# Sensors.net
KiCad netlist of a schematic drawn in Altium Designer
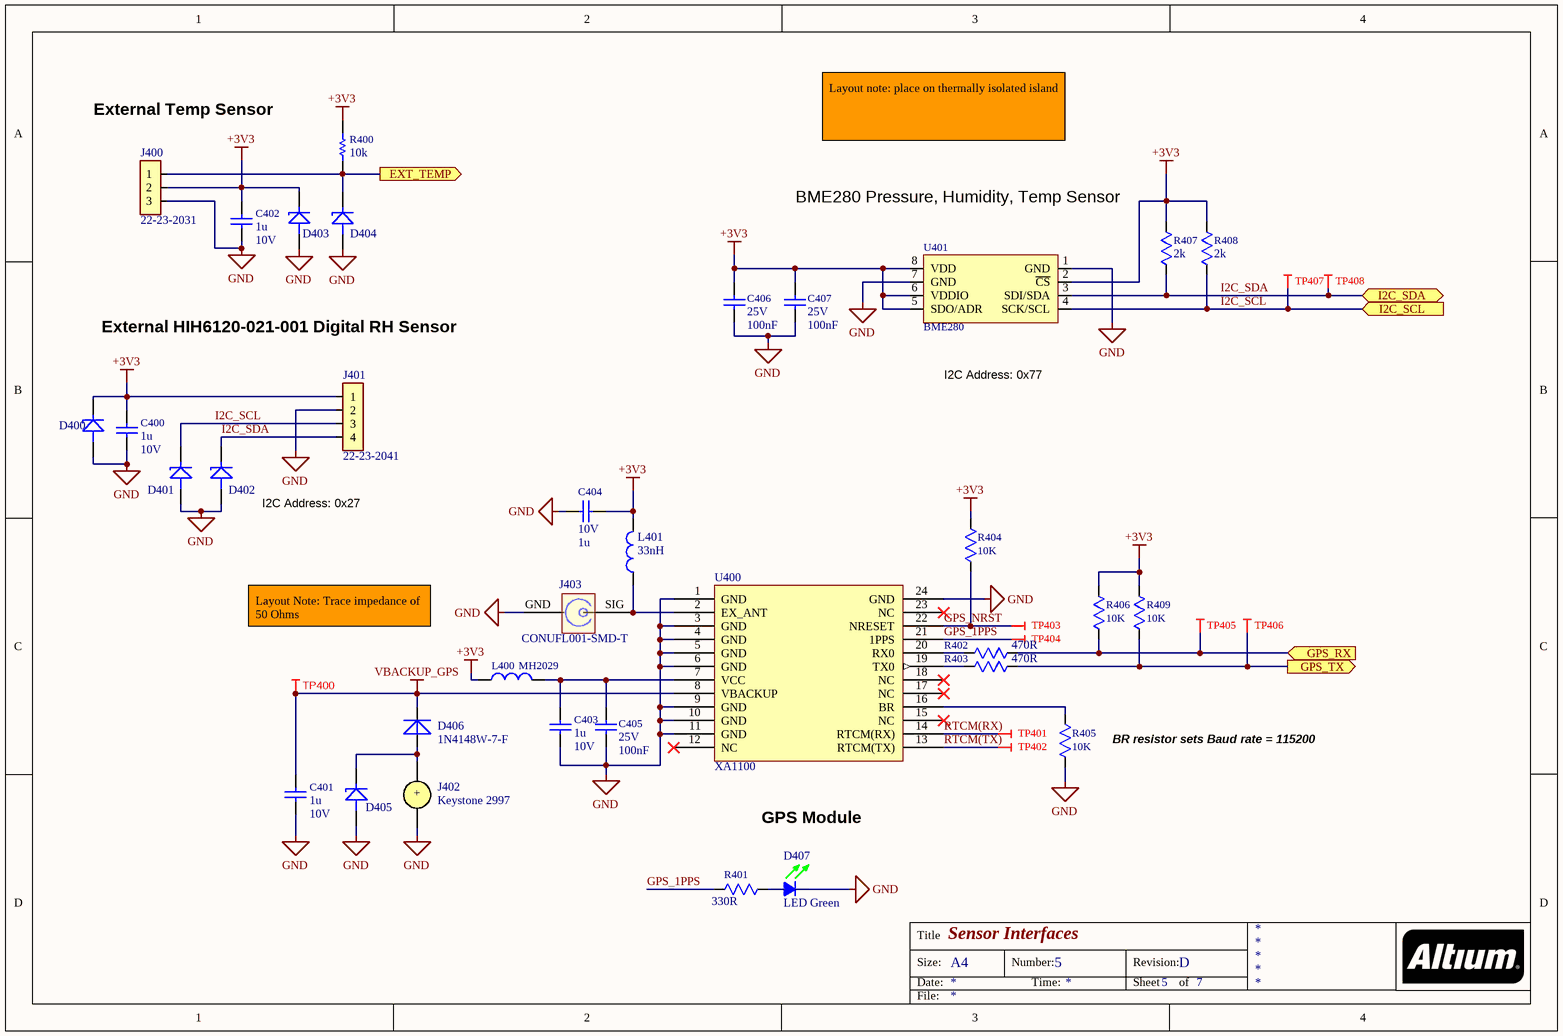
[diagram p0: Sensors.SchDoc]

(export (version "E")
  (design (tool "Eeschema 10.0.6"))
  (components
    (comp (ref "C400")
      (value "1u")
      (footprint "CAPC1005X06N")
      (description "CAP 4.7uF 10V ±10% X5R 0603")
      (fields
        (field (name "VOLTAGE") "10V")
        (field (name "MANUFACTURER PART NUMBER") "CL05A105MP5NNNC")
        (field (name "MANUFACTURER") "Samsung")
      )
      (libsource (lib "Capacitors") (part "4.7uF_0603_10V"))
    )
    (comp (ref "C401")
      (value "1u")
      (footprint "CAPC1005X06N")
      (description "CAP 4.7uF 10V ±10% X5R 0603")
      (fields
        (field (name "VOLTAGE") "10V")
        (field (name "MANUFACTURER PART NUMBER") "CL05A105MP5NNNC")
        (field (name "MANUFACTURER") "Samsung")
      )
      (libsource (lib "Capacitors") (part "4.7uF_0603_10V"))
    )
    (comp (ref "C402")
      (value "1u")
      (footprint "CAPC1005X06N")
      (description "CAP 4.7uF 10V ±10% X5R 0603")
      (fields
        (field (name "VOLTAGE") "10V")
        (field (name "MANUFACTURER PART NUMBER") "CL05A105MP5NNNC")
        (field (name "MANUFACTURER") "Samsung")
      )
      (libsource (lib "Capacitors") (part "4.7uF_0603_10V"))
    )
    (comp (ref "C403")
      (value "1u")
      (footprint "CAPC1005X06N")
      (description "CAP 4.7uF 10V ±10% X5R 0603")
      (fields
        (field (name "VOLTAGE") "10V")
        (field (name "MANUFACTURER PART NUMBER") "CL05A105MP5NNNC")
        (field (name "MANUFACTURER") "Samsung")
      )
      (libsource (lib "Capacitors") (part "4.7uF_0603_10V"))
    )
    (comp (ref "C404")
      (value "1u")
      (footprint "CAPC1005X06N")
      (description "CAP 4.7uF 10V ±10% X5R 0603")
      (fields
        (field (name "VOLTAGE") "10V")
        (field (name "MANUFACTURER PART NUMBER") "CL05A105MP5NNNC")
        (field (name "MANUFACTURER") "Samsung")
      )
      (libsource (lib "Capacitors") (part "4.7uF_0603_10V"))
    )
    (comp (ref "C405")
      (value "100nF")
      (footprint "CAPC1005X06N")
      (fields
        (field (name "VOLTAGE") "25V")
        (field (name "MANUFACTURER PART NUMBER") "CL05A104KA5NNNC")
        (field (name "MANUFACTURER") "Samsung")
        (field (name "Comment") "4.7uF")
      )
      (libsource (lib "Capacitors") (part "4.7uF_0603_10V"))
    )
    (comp (ref "C406")
      (value "100nF")
      (footprint "CAPC1005X06N")
      (fields
        (field (name "VOLTAGE") "25V")
        (field (name "MANUFACTURER PART NUMBER") "CL05A104KA5NNNC")
        (field (name "MANUFACTURER") "Samsung")
        (field (name "Comment") "4.7uF")
      )
      (libsource (lib "Capacitors") (part "4.7uF_0603_10V"))
    )
    (comp (ref "C407")
      (value "100nF")
      (footprint "CAPC1005X06N")
      (fields
        (field (name "VOLTAGE") "25V")
        (field (name "MANUFACTURER PART NUMBER") "CL05A104KA5NNNC")
        (field (name "MANUFACTURER") "Samsung")
        (field (name "Comment") "4.7uF")
      )
      (libsource (lib "Capacitors") (part "4.7uF_0603_10V"))
    )
    (comp (ref "D400")
      (value "3.3V TVS")
      (footprint "NXP PTVSxS1UR-Series (SOD123W)")
      (fields
        (field (name "MANUFACTURER") "Nexperia")
        (field (name "MANUFACTURER PART NUMBER") "PTVS3V3S1UTR,115")
      )
      (libsource (lib "FSM_2018") (part "NXP PTVSxS1UR-Series"))
    )
    (comp (ref "D401")
      (value "3.3V TVS")
      (footprint "NXP PTVSxS1UR-Series (SOD123W)")
      (fields
        (field (name "MANUFACTURER") "Nexperia")
        (field (name "MANUFACTURER PART NUMBER") "PTVS3V3S1UTR,115")
      )
      (libsource (lib "FSM_2018") (part "NXP PTVSxS1UR-Series"))
    )
    (comp (ref "D402")
      (value "3.3V TVS")
      (footprint "NXP PTVSxS1UR-Series (SOD123W)")
      (fields
        (field (name "MANUFACTURER") "Nexperia")
        (field (name "MANUFACTURER PART NUMBER") "PTVS3V3S1UTR,115")
      )
      (libsource (lib "FSM_2018") (part "NXP PTVSxS1UR-Series"))
    )
    (comp (ref "D403")
      (value "3.3V TVS")
      (footprint "NXP PTVSxS1UR-Series (SOD123W)")
      (fields
        (field (name "MANUFACTURER") "Nexperia")
        (field (name "MANUFACTURER PART NUMBER") "PTVS3V3S1UTR,115")
      )
      (libsource (lib "FSM_2018") (part "NXP PTVSxS1UR-Series"))
    )
    (comp (ref "D404")
      (value "3.3V TVS")
      (footprint "NXP PTVSxS1UR-Series (SOD123W)")
      (fields
        (field (name "MANUFACTURER") "Nexperia")
        (field (name "MANUFACTURER PART NUMBER") "PTVS3V3S1UTR,115")
      )
      (libsource (lib "FSM_2018") (part "NXP PTVSxS1UR-Series"))
    )
    (comp (ref "D405")
      (value "3.3V TVS")
      (footprint "NXP PTVSxS1UR-Series (SOD123W)")
      (fields
        (field (name "MANUFACTURER") "Nexperia")
        (field (name "MANUFACTURER PART NUMBER") "PTVS3V3S1UTR,115")
      )
      (libsource (lib "FSM_2018") (part "NXP PTVSxS1UR-Series"))
    )
    (comp (ref "D406")
      (value "1N4148W-FDICT-ND")
      (footprint "SOD-123FL_TVS")
      (description "300mA General Purpose")
      (fields
        (field (name "MANUFACTURER PART NUMBER") "1N4148W-7-F")
        (field (name "MANUFACTURER") "Diodes Incorporated")
      )
      (libsource (lib "Active") (part "Diode 300mA Gen Purp"))
    )
    (comp (ref "D407")
      (value "LED Green")
      (footprint "LED_0603")
      (description "LED Green Diffused 0603")
      (fields (field (name "MANUFACTURER") "Rohm") (field (name "MANUFACTURER PART NUMBER") "SML-D12M8WT86"))
      (libsource (lib "LEDs") (part "Green LED"))
    )
    (comp (ref "J400")
      (value "22-23-2031")
      (footprint "22-23-2031")
      (description "Connector Header Through Hole 3 position 0.100\" (2.54mm)")
      (fields (field (name "MANUFACTURER") "Molex") (field (name "MANUFACTURER PART NUMBER") "0022232031"))
      (libsource (lib "Gas Monitor Components") (part "22-23-2031"))
    )
    (comp (ref "J401")
      (value "22-23-2041")
      (footprint "22-23-2041")
      (description "Connector Header Through Hole 4 position 0.100\" (2.54mm)")
      (fields (field (name "MANUFACTURER") "Molex") (field (name "MANUFACTURER PART NUMBER") "0022232041"))
      (libsource (lib "Gas Monitor Components") (part "22-23-2041"))
    )
    (comp (ref "J402")
      (value "Keystone 2997")
      (footprint "2997 11.6mm COIN CELL")
      (description "DigiKey # 36-2997-ND")
      (fields
        (field (name "MANUFACTURER") "Keystone Electronics")
        (field (name "MANUFACTURER PART NUMBER") "2997")
      )
      (libsource (lib "Connectors-V") (part "30mm Coin Cell Holder"))
    )
    (comp (ref "J403")
      (value "uFl Connector")
      (footprint "CONUFL001-SMD-T")
      (description "CONUFL001-SMD-T")
      (fields
        (field (name "MANUFACTURER") "Linx Technologies")
        (field (name "MANUFACTURER PART NUMBER") "CONUFL001-SMD-T")
      )
      (libsource (lib "Gas Monitor Components") (part "uFl Connector"))
    )
    (comp (ref "L400")
      (value "MH2029")
      (footprint "L2012[0805]")
      (description "Ferrite,SMD,3A,30Ohm,0805")
      (fields
        (field (name "MANUFACTURER") "Bourns Inc.")
        (field (name "MANUFACTURER PART NUMBER") "MH2029-300Y")
      )
      (libsource (lib "Inductors") (part "Ferrite_MH2029_0805"))
    )
    (comp (ref "L401")
      (value "33nH")
      (footprint "L1608[0603]")
      (description "Fixed Inductor,SMD,33nH,550mA,132mOhmDCR,2.5GHz,0603")
      (fields
        (field (name "MANUFACTURER") "Murata")
        (field (name "MANUFACTURER PART NUMBER") "LQW18AN33NJ10D")
      )
      (libsource (lib "Inductors") (part "Inductor_33nH"))
    )
    (comp (ref "R400")
      (value "10k")
      (footprint "RESC1005X03N")
      (fields
        (field (name "MANUFACTURER") "Panasonic")
        (field (name "MANUFACTURER PART NUMBER") "ERJ-2RKF1002X")
        (field (name "Comment") "RES: GENERAL")
      )
      (libsource (lib "Santuary") (part "RES{colon} GENERAL"))
    )
    (comp (ref "R401")
      (value "330R")
      (footprint "R1608[0603] small")
      (description "RES 1K Ohm ±5%, 0.25W,1/4W 0603")
      (fields
        (field (name "MANUFACTURER") "Rohm")
        (field (name "MANUFACTURER PART NUMBER") "RC0603FR-07330RL")
      )
      (libsource (lib "Resistors") (part "1K00_0603_0.1W"))
    )
    (comp (ref "R402")
      (value "470R")
      (footprint "RESC1005X03N")
      (description "RES 1K Ohm ±5%, 0.25W,1/4W 0603")
      (fields
        (field (name "MANUFACTURER") "Panasonic")
        (field (name "MANUFACTURER PART NUMBER") "ERJ-2RKF4700X")
      )
      (libsource (lib "Resistors") (part "1K00_0603_0.1W"))
    )
    (comp (ref "R403")
      (value "470R")
      (footprint "RESC1005X03N")
      (description "RES 1K Ohm ±5%, 0.25W,1/4W 0603")
      (fields
        (field (name "MANUFACTURER") "Panasonic")
        (field (name "MANUFACTURER PART NUMBER") "ERJ-2RKF4700X")
      )
      (libsource (lib "Resistors") (part "1K00_0603_0.1W"))
    )
    (comp (ref "R404")
      (value "10K")
      (footprint "RESC1005X03N")
      (description "RES 1K Ohm ±5%, 0.25W,1/4W 0603")
      (fields
        (field (name "MANUFACTURER") "Panasonic")
        (field (name "MANUFACTURER PART NUMBER") "ERJ-2RKF1002X")
      )
      (libsource (lib "Resistors") (part "1K00_0603_0.1W"))
    )
    (comp (ref "R405")
      (value "10K")
      (footprint "RESC1005X03N")
      (description "RES 1K Ohm ±5%, 0.25W,1/4W 0603")
      (fields
        (field (name "MANUFACTURER") "Panasonic")
        (field (name "MANUFACTURER PART NUMBER") "ERJ-2RKF1002X")
      )
      (libsource (lib "Resistors") (part "1K00_0603_0.1W"))
    )
    (comp (ref "R406")
      (value "10K")
      (footprint "RESC1005X03N")
      (description "RES 1K Ohm ±5%, 0.25W,1/4W 0603")
      (fields
        (field (name "MANUFACTURER") "Panasonic")
        (field (name "MANUFACTURER PART NUMBER") "ERJ-2RKF1002X")
      )
      (libsource (lib "Resistors") (part "1K00_0603_0.1W"))
    )
    (comp (ref "R407")
      (value "2k")
      (footprint "R1005[0402]")
      (fields
        (field (name "MANUFACTURER") "Panasonic")
        (field (name "MANUFACTURER PART NUMBER") "ERJ-2RKF2001X")
        (field (name "Comment") "10K")
      )
      (libsource (lib "Resistors") (part "1K00_0603_0.1W"))
    )
    (comp (ref "R408")
      (value "2k")
      (footprint "R1005[0402]")
      (fields
        (field (name "MANUFACTURER") "Panasonic")
        (field (name "MANUFACTURER PART NUMBER") "ERJ-2RKF2001X")
        (field (name "Comment") "10K")
      )
      (libsource (lib "Resistors") (part "1K00_0603_0.1W"))
    )
    (comp (ref "R409")
      (value "10K")
      (footprint "RESC1005X03N")
      (description "RES 1K Ohm ±5%, 0.25W,1/4W 0603")
      (fields
        (field (name "MANUFACTURER") "Panasonic")
        (field (name "MANUFACTURER PART NUMBER") "ERJ-2RKF1002X")
      )
      (libsource (lib "Resistors") (part "1K00_0603_0.1W"))
    )
    (comp (ref "TP400")
      (value "PAD")
      (footprint "TP_SMD_39MIL")
      (description "SMD Test Pad")
      (fields (field (name "MANUFACTURER") "No P/N Required"))
      (libsource (lib "Connectors") (part "TP_SMD_39MIL"))
    )
    (comp (ref "TP401")
      (value "PAD")
      (footprint "TP_SMD_39MIL")
      (description "SMD Test Pad")
      (fields (field (name "MANUFACTURER") "No P/N Required"))
      (libsource (lib "Connectors") (part "TP_SMD_39MIL"))
    )
    (comp (ref "TP402")
      (value "PAD")
      (footprint "TP_SMD_39MIL")
      (description "SMD Test Pad")
      (fields (field (name "MANUFACTURER") "No P/N Required"))
      (libsource (lib "Connectors") (part "TP_SMD_39MIL"))
    )
    (comp (ref "TP403")
      (value "PAD")
      (footprint "TP_SMD_39MIL")
      (description "SMD Test Pad")
      (fields (field (name "MANUFACTURER") "No P/N Required"))
      (libsource (lib "Connectors") (part "TP_SMD_39MIL"))
    )
    (comp (ref "TP404")
      (value "PAD")
      (footprint "TP_SMD_45MIL")
      (description "SMD Test Pad")
      (fields (field (name "MANUFACTURER") "No P/N Required"))
      (libsource (lib "Connectors") (part "TP_SMD_45MIL"))
    )
    (comp (ref "TP405")
      (value "PAD")
      (footprint "TP_SMD_39MIL")
      (description "SMD Test Pad")
      (fields (field (name "MANUFACTURER") "No P/N Required"))
      (libsource (lib "Connectors") (part "TP_SMD_39MIL"))
    )
    (comp (ref "TP406")
      (value "PAD")
      (footprint "TP_SMD_39MIL")
      (description "SMD Test Pad")
      (fields (field (name "MANUFACTURER") "No P/N Required"))
      (libsource (lib "Connectors") (part "TP_SMD_39MIL"))
    )
    (comp (ref "TP407")
      (value "PAD")
      (footprint "TP_SMD_39MIL")
      (description "SMD Test Pad")
      (fields (field (name "MANUFACTURER") "No P/N Required"))
      (libsource (lib "Connectors") (part "TP_SMD_39MIL"))
    )
    (comp (ref "TP408")
      (value "PAD")
      (footprint "TP_SMD_39MIL")
      (description "SMD Test Pad")
      (fields (field (name "MANUFACTURER") "No P/N Required"))
      (libsource (lib "Connectors") (part "TP_SMD_39MIL"))
    )
    (comp (ref "U400")
      (value "XA1100")
      (footprint "XA1100")
      (description "GPS Module")
      (fields
        (field (name "MANUFACTURER PART NUMBER") "XA1100_1103872")
        (field (name "MANUFACTURER") "Sierra Wireless")
      )
      (libsource (lib "Gas Monitor Components") (part "XA1100"))
    )
    (comp (ref "U401")
      (value "BME280")
      (footprint "BME280")
      (description "SENSOR Humidity Temperature 0 ~ 100% RH I²C SPI ±3% 1s 8-Pin LGA")
      (fields (field (name "MANUFACTURER") "Bosch"))
      (libsource (lib "Sensors") (part "BME280"))
    )
  )
  (nets
    (net (code "1") (name "+3V3") (class "Default")
      (node (ref "C400") (pin "2") (pintype "passive"))
      (node (ref "C402") (pin "2") (pintype "passive"))
      (node (ref "C404") (pin "1") (pintype "passive"))
      (node (ref "C406") (pin "2") (pintype "passive"))
      (node (ref "C407") (pin "2") (pintype "passive"))
      (node (ref "D400") (pin "1") (pinfunction "1_1") (pintype "passive"))
      (node (ref "D403") (pin "1") (pinfunction "1_1") (pintype "passive"))
      (node (ref "J400") (pin "2") (pinfunction "2_2") (pintype "passive"))
      (node (ref "J401") (pin "1") (pinfunction "1_1") (pintype "passive"))
      (node (ref "L400") (pin "1") (pintype "passive"))
      (node (ref "L401") (pin "2") (pintype "passive"))
      (node (ref "R400") (pin "2") (pinfunction "2_2") (pintype "passive"))
      (node (ref "R404") (pin "2") (pintype "passive"))
      (node (ref "R406") (pin "2") (pintype "passive"))
      (node (ref "R407") (pin "2") (pintype "passive"))
      (node (ref "R408") (pin "2") (pintype "passive"))
      (node (ref "R409") (pin "2") (pintype "passive"))
      (node (ref "U401") (pin "2") (pinfunction "~{CS}_2") (pintype "passive"))
      (node (ref "U401") (pin "5") (pinfunction "SDO/ADR_5") (pintype "passive"))
      (node (ref "U401") (pin "6") (pinfunction "VDDIO_6") (pintype "passive"))
      (node (ref "U401") (pin "8") (pinfunction "VDD_8") (pintype "passive"))
    )
    (net (code "2") (name "/EXT_TEMP") (class "Default")
      (node (ref "D404") (pin "1") (pinfunction "1_1") (pintype "passive"))
      (node (ref "J400") (pin "1") (pinfunction "1_1") (pintype "passive"))
      (node (ref "R400") (pin "1") (pinfunction "1_1") (pintype "passive"))
    )
    (net (code "3") (name "/GPS_1PPS") (class "Default")
      (node (ref "R401") (pin "2") (pintype "passive"))
      (node (ref "TP404") (pin "1") (pintype "passive"))
      (node (ref "U400") (pin "21") (pinfunction "1PPS_21") (pintype "passive"))
    )
    (net (code "4") (name "/GPS_NRST") (class "Default")
      (node (ref "R404") (pin "1") (pintype "passive"))
      (node (ref "TP403") (pin "1") (pintype "passive"))
      (node (ref "U400") (pin "22") (pinfunction "NRESET_22") (pintype "passive"))
    )
    (net (code "5") (name "/GPS_RX") (class "Default")
      (node (ref "R402") (pin "1") (pintype "passive"))
      (node (ref "R406") (pin "1") (pintype "passive"))
      (node (ref "TP405") (pin "1") (pintype "passive"))
    )
    (net (code "6") (name "/GPS_TX") (class "Default")
      (node (ref "R403") (pin "1") (pintype "passive"))
      (node (ref "R409") (pin "1") (pintype "passive"))
      (node (ref "TP406") (pin "1") (pintype "passive"))
    )
    (net (code "7") (name "/I2C_SCL") (class "Default")
      (node (ref "D401") (pin "1") (pinfunction "1_1") (pintype "passive"))
      (node (ref "J401") (pin "3") (pinfunction "3_3") (pintype "passive"))
      (node (ref "R408") (pin "1") (pintype "passive"))
      (node (ref "TP407") (pin "1") (pintype "passive"))
      (node (ref "U401") (pin "4") (pinfunction "SCK/SCL_4") (pintype "passive"))
    )
    (net (code "8") (name "/I2C_SDA") (class "Default")
      (node (ref "D402") (pin "1") (pinfunction "1_1") (pintype "passive"))
      (node (ref "J401") (pin "4") (pinfunction "4_4") (pintype "passive"))
      (node (ref "R407") (pin "1") (pintype "passive"))
      (node (ref "TP408") (pin "1") (pintype "passive"))
      (node (ref "U401") (pin "3") (pinfunction "SDI/SDA_3") (pintype "passive"))
    )
    (net (code "9") (name "/RTCM(RX)") (class "Default")
      (node (ref "TP401") (pin "1") (pintype "passive"))
      (node (ref "U400") (pin "14") (pinfunction "RTCM(RX)_14") (pintype "passive"))
    )
    (net (code "10") (name "/RTCM(TX)") (class "Default")
      (node (ref "TP402") (pin "1") (pintype "passive"))
      (node (ref "U400") (pin "13") (pinfunction "RTCM(TX)_13") (pintype "passive"))
    )
    (net (code "11") (name "GND") (class "Default")
      (node (ref "C400") (pin "1") (pintype "passive"))
      (node (ref "C401") (pin "1") (pintype "passive"))
      (node (ref "C402") (pin "1") (pintype "passive"))
      (node (ref "C403") (pin "1") (pintype "passive"))
      (node (ref "C404") (pin "2") (pintype "passive"))
      (node (ref "C405") (pin "1") (pintype "passive"))
      (node (ref "C406") (pin "1") (pintype "passive"))
      (node (ref "C407") (pin "1") (pintype "passive"))
      (node (ref "D400") (pin "2") (pinfunction "2_2") (pintype "passive"))
      (node (ref "D401") (pin "2") (pinfunction "2_2") (pintype "passive"))
      (node (ref "D402") (pin "2") (pinfunction "2_2") (pintype "passive"))
      (node (ref "D403") (pin "2") (pinfunction "2_2") (pintype "passive"))
      (node (ref "D404") (pin "2") (pinfunction "2_2") (pintype "passive"))
      (node (ref "D405") (pin "2") (pinfunction "2_2") (pintype "passive"))
      (node (ref "D407") (pin "2") (pintype "passive"))
      (node (ref "J400") (pin "3") (pinfunction "3_3") (pintype "passive"))
      (node (ref "J401") (pin "2") (pinfunction "2_2") (pintype "passive"))
      (node (ref "J402") (pin "2") (pinfunction "2_2") (pintype "passive"))
      (node (ref "J403") (pin "GND") (pinfunction "GND_GND") (pintype "passive"))
      (node (ref "R405") (pin "1") (pintype "passive"))
      (node (ref "U400") (pin "1") (pinfunction "GND_1") (pintype "power_in"))
      (node (ref "U400") (pin "10") (pinfunction "GND_10") (pintype "power_in"))
      (node (ref "U400") (pin "11") (pinfunction "GND_11") (pintype "power_in"))
      (node (ref "U400") (pin "24") (pinfunction "GND_24") (pintype "power_in"))
      (node (ref "U400") (pin "3") (pinfunction "GND_3") (pintype "power_in"))
      (node (ref "U400") (pin "4") (pinfunction "GND_4") (pintype "power_in"))
      (node (ref "U400") (pin "5") (pinfunction "GND_5") (pintype "power_in"))
      (node (ref "U400") (pin "6") (pinfunction "GND_6") (pintype "power_in"))
      (node (ref "U400") (pin "9") (pinfunction "GND_9") (pintype "power_in"))
      (node (ref "U401") (pin "1") (pinfunction "GND_1") (pintype "passive"))
      (node (ref "U401") (pin "7") (pinfunction "GND_7") (pintype "passive"))
    )
    (net (code "12") (name "Net-(D407-Pad1)") (class "Default")
      (node (ref "D407") (pin "1") (pintype "passive"))
      (node (ref "R401") (pin "1") (pintype "passive"))
    )
    (net (code "13") (name "Net-(J402-+)") (class "Default")
      (node (ref "D405") (pin "1") (pinfunction "1_1") (pintype "passive"))
      (node (ref "D406") (pin "1") (pintype "passive"))
      (node (ref "J402") (pin "1") (pinfunction "+_1") (pintype "passive"))
    )
    (net (code "14") (name "Net-(U400-BR)") (class "Default")
      (node (ref "R405") (pin "2") (pintype "passive"))
      (node (ref "U400") (pin "16") (pinfunction "BR_16") (pintype "passive"))
    )
    (net (code "15") (name "Net-(U400-EX_ANT)") (class "Default")
      (node (ref "J403") (pin "SIG") (pinfunction "SIG_SIG") (pintype "passive"))
      (node (ref "L401") (pin "1") (pintype "passive"))
      (node (ref "U400") (pin "2") (pinfunction "EX_ANT_2") (pintype "passive"))
    )
    (net (code "16") (name "Net-(U400-RX0)") (class "Default")
      (node (ref "R402") (pin "2") (pintype "passive"))
      (node (ref "U400") (pin "20") (pinfunction "RX0_20") (pintype "passive"))
    )
    (net (code "17") (name "Net-(U400-TX0)") (class "Default")
      (node (ref "R403") (pin "2") (pintype "passive"))
      (node (ref "U400") (pin "19") (pinfunction "TX0_19") (pintype "output"))
    )
    (net (code "18") (name "Net-(U400-VCC)") (class "Default")
      (node (ref "C403") (pin "2") (pintype "passive"))
      (node (ref "C405") (pin "2") (pintype "passive"))
      (node (ref "L400") (pin "2") (pintype "passive"))
      (node (ref "U400") (pin "7") (pinfunction "VCC_7") (pintype "power_in"))
    )
    (net (code "19") (name "VBACKUP_GPS") (class "Default")
      (node (ref "C401") (pin "2") (pintype "passive"))
      (node (ref "D406") (pin "2") (pintype "passive"))
      (node (ref "TP400") (pin "1") (pintype "passive"))
      (node (ref "U400") (pin "8") (pinfunction "VBACKUP_8") (pintype "power_in"))
    )
    (net (code "20") (name "unconnected-(U400-NC-Pad12)") (class "Default")
      (node (ref "U400") (pin "12") (pinfunction "NC_12") (pintype "passive+no_connect"))
    )
    (net (code "21") (name "unconnected-(U400-NC-Pad15)") (class "Default")
      (node (ref "U400") (pin "15") (pinfunction "NC_15") (pintype "passive+no_connect"))
    )
    (net (code "22") (name "unconnected-(U400-NC-Pad17)") (class "Default")
      (node (ref "U400") (pin "17") (pinfunction "NC_17") (pintype "passive+no_connect"))
    )
    (net (code "23") (name "unconnected-(U400-NC-Pad18)") (class "Default")
      (node (ref "U400") (pin "18") (pinfunction "NC_18") (pintype "passive+no_connect"))
    )
    (net (code "24") (name "unconnected-(U400-NC-Pad23)") (class "Default")
      (node (ref "U400") (pin "23") (pinfunction "NC_23") (pintype "passive+no_connect"))
    )
  )
)
